# Arduino-Pro.net
KiCad netlist of a schematic drawn in EAGLE
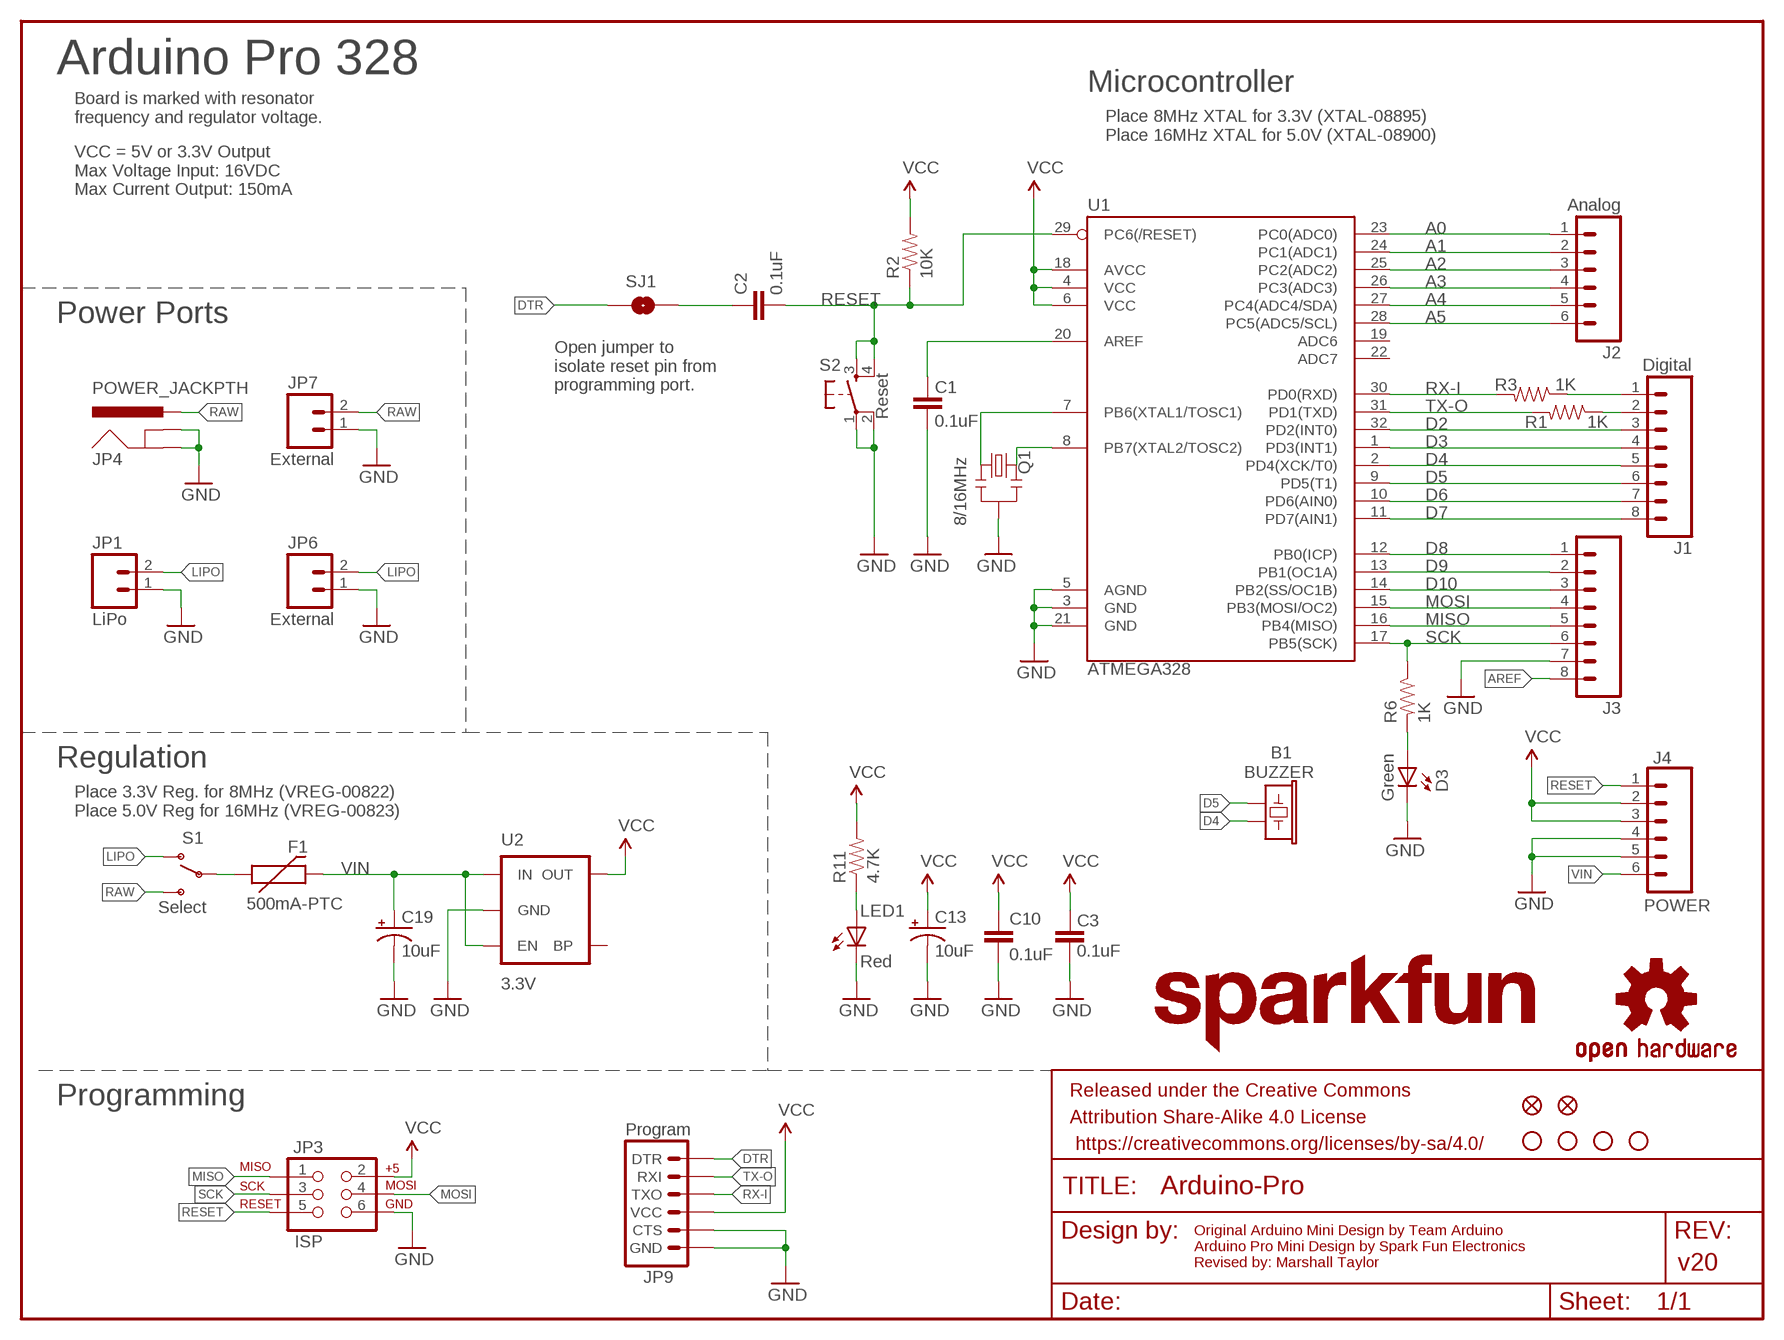
[diagram p0: schematic, sheet 1]

(export (version "E")
  (design (tool "Eeschema 10.0.6"))
  (components
    (comp (ref "B1")
      (value "BUZZER")
      (footprint "eagle-import:BUZZER-12MM-NS-KIT")
      (libsource (lib "eagle-import") (part "BUZZERPTH-NS-KIT"))
    )
    (comp (ref "C1")
      (value "0.1uF")
      (footprint "eagle-import:0402-CAP")
      (libsource (lib "eagle-import") (part "CAP0402-CAP"))
    )
    (comp (ref "C2")
      (value "0.1uF")
      (footprint "eagle-import:0402-CAP")
      (libsource (lib "eagle-import") (part "CAP0402-CAP"))
    )
    (comp (ref "C3")
      (value "0.1uF")
      (footprint "eagle-import:0402-CAP")
      (libsource (lib "eagle-import") (part "CAP0402-CAP"))
    )
    (comp (ref "C10")
      (value "0.1uF")
      (footprint "eagle-import:0402-CAP")
      (libsource (lib "eagle-import") (part "CAP0402-CAP"))
    )
    (comp (ref "C13")
      (value "10uF")
      (footprint "eagle-import:EIA3216")
      (libsource (lib "eagle-import") (part "CAP_POL1206"))
    )
    (comp (ref "C19")
      (value "10uF")
      (footprint "eagle-import:EIA3216")
      (libsource (lib "eagle-import") (part "CAP_POL1206"))
    )
    (comp (ref "D3")
      (value "Green")
      (footprint "eagle-import:LED-0603")
      (libsource (lib "eagle-import") (part "LED0603"))
    )
    (comp (ref "F1")
      (value "500mA-PTC")
      (footprint "eagle-import:PTC-1206")
      (libsource (lib "eagle-import") (part "PTCSMD"))
    )
    (comp (ref "FRAME2")
      (value "FRAME-LETTER")
      (footprint "eagle-import:CREATIVE_COMMONS")
      (libsource (lib "eagle-import") (part "FRAME-LETTER"))
    )
    (comp (ref "J1")
      (value "Digital")
      (footprint "eagle-import:1X08")
      (libsource (lib "eagle-import") (part "M081X08"))
    )
    (comp (ref "J2")
      (value "Analog")
      (footprint "eagle-import:1X06")
      (libsource (lib "eagle-import") (part "M06SIP"))
    )
    (comp (ref "J3")
      (value "M081X08")
      (footprint "eagle-import:1X08")
      (libsource (lib "eagle-import") (part "M081X08"))
    )
    (comp (ref "J4")
      (value "POWER")
      (footprint "eagle-import:1X06")
      (libsource (lib "eagle-import") (part "M06SIP"))
    )
    (comp (ref "JP1")
      (value "LiPo")
      (footprint "eagle-import:JST-2-SMD")
      (libsource (lib "eagle-import") (part "M02-JST-2MM-SMT"))
    )
    (comp (ref "JP2")
      (value "FIDUCIAL1X2.5")
      (footprint "eagle-import:FIDUCIAL-1X2.5")
      (libsource (lib "eagle-import") (part "FIDUCIAL1X2.5"))
    )
    (comp (ref "JP3")
      (value "ISP")
      (footprint "eagle-import:2X3")
      (libsource (lib "eagle-import") (part "AVR_SPI_PRG_6PTH"))
    )
    (comp (ref "JP4")
      (value "POWER_JACKPTH")
      (footprint "eagle-import:POWER_JACK_PTH")
      (libsource (lib "eagle-import") (part "POWER_JACKPTH"))
    )
    (comp (ref "JP5")
      (value "FIDUCIAL1X2.5")
      (footprint "eagle-import:FIDUCIAL-1X2.5")
      (libsource (lib "eagle-import") (part "FIDUCIAL1X2.5"))
    )
    (comp (ref "JP6")
      (value "External")
      (footprint "eagle-import:1X02")
      (libsource (lib "eagle-import") (part "M02PTH"))
    )
    (comp (ref "JP7")
      (value "External")
      (footprint "eagle-import:1X02")
      (libsource (lib "eagle-import") (part "M02PTH"))
    )
    (comp (ref "JP9")
      (value "Program")
      (footprint "eagle-import:1X06-SMD")
      (libsource (lib "eagle-import") (part "ARDUINO_SERIAL_PROGRAMSMD"))
    )
    (comp (ref "LED1")
      (value "Red")
      (footprint "eagle-import:LED-0603")
      (libsource (lib "eagle-import") (part "LED0603"))
    )
    (comp (ref "Q1")
      (value "8/16MHz")
      (footprint "eagle-import:RESONATOR-SMD")
      (libsource (lib "eagle-import") (part "RESONATORSMD"))
    )
    (comp (ref "R1")
      (value "1K")
      (footprint "eagle-import:0402-RES")
      (libsource (lib "eagle-import") (part "RESISTOR0402-RES"))
    )
    (comp (ref "R2")
      (value "10K")
      (footprint "eagle-import:0402-RES")
      (libsource (lib "eagle-import") (part "RESISTOR0402-RES"))
    )
    (comp (ref "R3")
      (value "1K")
      (footprint "eagle-import:0402-RES")
      (libsource (lib "eagle-import") (part "RESISTOR0402-RES"))
    )
    (comp (ref "R6")
      (value "1K")
      (footprint "eagle-import:0402-RES")
      (libsource (lib "eagle-import") (part "RESISTOR0402-RES"))
    )
    (comp (ref "R11")
      (value "4.7K")
      (footprint "eagle-import:0402-RES")
      (libsource (lib "eagle-import") (part "RESISTOR0402-RES"))
    )
    (comp (ref "S1")
      (value "Select")
      (footprint "eagle-import:SWITCH-SPST-SMD-A")
      (libsource (lib "eagle-import") (part "SWITCH-SPST-SMD-A"))
    )
    (comp (ref "S2")
      (value "Reset")
      (footprint "eagle-import:TACTILE_SWITCH_SMD")
      (libsource (lib "eagle-import") (part "TAC_SWITCHSMD"))
    )
    (comp (ref "SJ1")
      (value "SOLDERJUMPERNC3")
      (footprint "eagle-import:SJ_2S-NOTRACE")
      (libsource (lib "eagle-import") (part "SOLDERJUMPERNC2"))
    )
    (comp (ref "U$1")
      (value "STAND-OFF")
      (footprint "eagle-import:STAND-OFF")
      (libsource (lib "eagle-import") (part "STAND-OFF"))
    )
    (comp (ref "U$3")
      (value "STAND-OFF")
      (footprint "eagle-import:STAND-OFF")
      (libsource (lib "eagle-import") (part "STAND-OFF"))
    )
    (comp (ref "U$9")
      (value "STAND-OFF")
      (footprint "eagle-import:STAND-OFF")
      (libsource (lib "eagle-import") (part "STAND-OFF"))
    )
    (comp (ref "U$10")
      (value "STAND-OFF")
      (footprint "eagle-import:STAND-OFF")
      (libsource (lib "eagle-import") (part "STAND-OFF"))
    )
    (comp (ref "U1")
      (value "ATMEGA328")
      (footprint "eagle-import:TQFP32-08")
      (libsource (lib "eagle-import") (part "ATMEGA168"))
    )
    (comp (ref "U2")
      (value "3.3V")
      (footprint "eagle-import:SOT23-5")
      (libsource (lib "eagle-import") (part "V_REG_LDOSMD"))
    )
  )
  (nets
    (net (code "1") (name "/A0") (class "Default")
      (node (ref "J2") (pin "1") (pinfunction "1_1") (pintype "passive"))
      (node (ref "U1") (pin "23") (pinfunction "PC0(ADC0)_23") (pintype "bidirectional"))
    )
    (net (code "2") (name "/A1") (class "Default")
      (node (ref "J2") (pin "2") (pinfunction "2_2") (pintype "passive"))
      (node (ref "U1") (pin "24") (pinfunction "PC1(ADC1)_24") (pintype "bidirectional"))
    )
    (net (code "3") (name "/A2") (class "Default")
      (node (ref "J2") (pin "3") (pinfunction "3_3") (pintype "passive"))
      (node (ref "U1") (pin "25") (pinfunction "PC2(ADC2)_25") (pintype "bidirectional"))
    )
    (net (code "4") (name "/A3") (class "Default")
      (node (ref "J2") (pin "4") (pinfunction "4_4") (pintype "passive"))
      (node (ref "U1") (pin "26") (pinfunction "PC3(ADC3)_26") (pintype "bidirectional"))
    )
    (net (code "5") (name "/A4") (class "Default")
      (node (ref "J2") (pin "5") (pinfunction "5_5") (pintype "passive"))
      (node (ref "U1") (pin "27") (pinfunction "PC4(ADC4/SDA)_27") (pintype "bidirectional"))
    )
    (net (code "6") (name "/A5") (class "Default")
      (node (ref "J2") (pin "6") (pinfunction "6_6") (pintype "passive"))
      (node (ref "U1") (pin "28") (pinfunction "PC5(ADC5/SCL)_28") (pintype "bidirectional"))
    )
    (net (code "7") (name "/D2") (class "Default")
      (node (ref "J1") (pin "3") (pinfunction "3_3") (pintype "passive"))
      (node (ref "U1") (pin "32") (pinfunction "PD2(INT0)_32") (pintype "bidirectional"))
    )
    (net (code "8") (name "/D3") (class "Default")
      (node (ref "J1") (pin "4") (pinfunction "4_4") (pintype "passive"))
      (node (ref "U1") (pin "1") (pinfunction "PD3(INT1)_1") (pintype "bidirectional"))
    )
    (net (code "9") (name "/D6") (class "Default")
      (node (ref "J1") (pin "7") (pinfunction "7_7") (pintype "passive"))
      (node (ref "U1") (pin "10") (pinfunction "PD6(AIN0)_10") (pintype "bidirectional"))
    )
    (net (code "10") (name "/D7") (class "Default")
      (node (ref "J1") (pin "8") (pinfunction "8_8") (pintype "passive"))
      (node (ref "U1") (pin "11") (pinfunction "PD7(AIN1)_11") (pintype "bidirectional"))
    )
    (net (code "11") (name "/D8") (class "Default")
      (node (ref "J3") (pin "1") (pinfunction "1_1") (pintype "passive"))
      (node (ref "U1") (pin "12") (pinfunction "PB0(ICP)_12") (pintype "bidirectional"))
    )
    (net (code "12") (name "/D9") (class "Default")
      (node (ref "J3") (pin "2") (pinfunction "2_2") (pintype "passive"))
      (node (ref "U1") (pin "13") (pinfunction "PB1(OC1A)_13") (pintype "bidirectional"))
    )
    (net (code "13") (name "/D10") (class "Default")
      (node (ref "J3") (pin "3") (pinfunction "3_3") (pintype "passive"))
      (node (ref "U1") (pin "14") (pinfunction "PB2(SS/OC1B)_14") (pintype "bidirectional"))
    )
    (net (code "14") (name "AREF") (class "Default")
      (node (ref "C1") (pin "2") (pinfunction "2_2") (pintype "passive"))
      (node (ref "J3") (pin "8") (pinfunction "8_8") (pintype "passive"))
      (node (ref "U1") (pin "20") (pinfunction "AREF_20") (pintype "bidirectional"))
    )
    (net (code "15") (name "D4") (class "Default")
      (node (ref "B1") (pin "-") (pinfunction "2_-") (pintype "passive"))
      (node (ref "J1") (pin "5") (pinfunction "5_5") (pintype "passive"))
      (node (ref "U1") (pin "2") (pinfunction "PD4(XCK/T0)_2") (pintype "bidirectional"))
    )
    (net (code "16") (name "D5") (class "Default")
      (node (ref "B1") (pin "+") (pinfunction "1_+") (pintype "passive"))
      (node (ref "J1") (pin "6") (pinfunction "6_6") (pintype "passive"))
      (node (ref "U1") (pin "9") (pinfunction "PD5(T1)_9") (pintype "bidirectional"))
    )
    (net (code "17") (name "DTR") (class "Default")
      (node (ref "JP9") (pin "1") (pinfunction "DTR_1") (pintype "passive"))
      (node (ref "SJ1") (pin "1") (pinfunction "1_1") (pintype "passive"))
    )
    (net (code "18") (name "GND") (class "Default")
      (node (ref "C1") (pin "1") (pinfunction "1_1") (pintype "passive"))
      (node (ref "C10") (pin "2") (pinfunction "2_2") (pintype "passive"))
      (node (ref "C13") (pin "C") (pinfunction "-_C") (pintype "passive"))
      (node (ref "C19") (pin "C") (pinfunction "-_C") (pintype "passive"))
      (node (ref "C3") (pin "1") (pinfunction "1_1") (pintype "passive"))
      (node (ref "D3") (pin "C") (pinfunction "C_C") (pintype "passive"))
      (node (ref "J3") (pin "7") (pinfunction "7_7") (pintype "passive"))
      (node (ref "J4") (pin "4") (pinfunction "4_4") (pintype "passive"))
      (node (ref "J4") (pin "5") (pinfunction "5_5") (pintype "passive"))
      (node (ref "JP1") (pin "1") (pinfunction "1_1") (pintype "passive"))
      (node (ref "JP3") (pin "6") (pinfunction "6_6") (pintype "passive"))
      (node (ref "JP4") (pin "GND") (pinfunction "GND_GND") (pintype "bidirectional"))
      (node (ref "JP4") (pin "GNDBREAK") (pinfunction "GNDBREAK_GNDBREAK") (pintype "bidirectional"))
      (node (ref "JP6") (pin "1") (pinfunction "1_1") (pintype "passive"))
      (node (ref "JP7") (pin "1") (pinfunction "1_1") (pintype "passive"))
      (node (ref "JP9") (pin "5") (pinfunction "CTS_5") (pintype "passive"))
      (node (ref "JP9") (pin "6") (pinfunction "GND_6") (pintype "passive"))
      (node (ref "LED1") (pin "C") (pinfunction "C_C") (pintype "passive"))
      (node (ref "Q1") (pin "2") (pinfunction "2_2") (pintype "passive"))
      (node (ref "S2") (pin "1") (pinfunction "1_1") (pintype "passive"))
      (node (ref "S2") (pin "2") (pinfunction "2_2") (pintype "passive"))
      (node (ref "U1") (pin "21") (pinfunction "GND_21") (pintype "bidirectional"))
      (node (ref "U1") (pin "3") (pinfunction "GND_3") (pintype "bidirectional"))
      (node (ref "U1") (pin "5") (pinfunction "AGND_5") (pintype "bidirectional"))
      (node (ref "U2") (pin "2") (pinfunction "GND_2") (pintype "input"))
    )
    (net (code "19") (name "LIPO") (class "Default")
      (node (ref "JP1") (pin "2") (pinfunction "2_2") (pintype "passive"))
      (node (ref "JP6") (pin "2") (pinfunction "2_2") (pintype "passive"))
      (node (ref "S1") (pin "1") (pinfunction "O_1") (pintype "passive"))
    )
    (net (code "20") (name "MISO") (class "Default")
      (node (ref "J3") (pin "5") (pinfunction "5_5") (pintype "passive"))
      (node (ref "JP3") (pin "1") (pinfunction "1_1") (pintype "passive"))
      (node (ref "U1") (pin "16") (pinfunction "PB4(MISO)_16") (pintype "bidirectional"))
    )
    (net (code "21") (name "MOSI") (class "Default")
      (node (ref "J3") (pin "4") (pinfunction "4_4") (pintype "passive"))
      (node (ref "JP3") (pin "4") (pinfunction "4_4") (pintype "passive"))
      (node (ref "U1") (pin "15") (pinfunction "PB3(MOSI/OC2)_15") (pintype "bidirectional"))
    )
    (net (code "22") (name "Net-(C2-Pad1)") (class "Default")
      (node (ref "C2") (pin "1") (pinfunction "1_1") (pintype "passive"))
      (node (ref "SJ1") (pin "2") (pinfunction "2_2") (pintype "passive"))
    )
    (net (code "23") (name "Net-(D3-PadA)") (class "Default")
      (node (ref "D3") (pin "A") (pinfunction "A_A") (pintype "passive"))
      (node (ref "R6") (pin "2") (pinfunction "2_2") (pintype "passive"))
    )
    (net (code "24") (name "Net-(J1-Pad1)") (class "Default")
      (node (ref "J1") (pin "1") (pinfunction "1_1") (pintype "passive"))
      (node (ref "R3") (pin "1") (pinfunction "1_1") (pintype "passive"))
    )
    (net (code "25") (name "Net-(J1-Pad2)") (class "Default")
      (node (ref "J1") (pin "2") (pinfunction "2_2") (pintype "passive"))
      (node (ref "R1") (pin "1") (pinfunction "1_1") (pintype "passive"))
    )
    (net (code "26") (name "Net-(LED1-PadA)") (class "Default")
      (node (ref "LED1") (pin "A") (pinfunction "A_A") (pintype "passive"))
      (node (ref "R11") (pin "1") (pinfunction "1_1") (pintype "passive"))
    )
    (net (code "27") (name "Net-(S1-P)") (class "Default")
      (node (ref "F1") (pin "1") (pinfunction "1_1") (pintype "bidirectional"))
      (node (ref "S1") (pin "2") (pinfunction "P_2") (pintype "passive"))
    )
    (net (code "28") (name "Net-(U1-PB6(XTAL1{slash}TOSC1))") (class "Default")
      (node (ref "Q1") (pin "3") (pinfunction "3_3") (pintype "passive"))
      (node (ref "U1") (pin "7") (pinfunction "PB6(XTAL1/TOSC1)_7") (pintype "bidirectional"))
    )
    (net (code "29") (name "Net-(U1-PB7(XTAL2{slash}TOSC2))") (class "Default")
      (node (ref "Q1") (pin "1") (pinfunction "1_1") (pintype "passive"))
      (node (ref "U1") (pin "8") (pinfunction "PB7(XTAL2/TOSC2)_8") (pintype "bidirectional"))
    )
    (net (code "30") (name "RAW") (class "Default")
      (node (ref "JP4") (pin "PWR") (pinfunction "PWR_PWR") (pintype "bidirectional"))
      (node (ref "JP7") (pin "2") (pinfunction "2_2") (pintype "passive"))
      (node (ref "S1") (pin "3") (pinfunction "S_3") (pintype "passive"))
    )
    (net (code "31") (name "RESET") (class "Default")
      (node (ref "C2") (pin "2") (pinfunction "2_2") (pintype "passive"))
      (node (ref "J4") (pin "1") (pinfunction "1_1") (pintype "passive"))
      (node (ref "JP3") (pin "5") (pinfunction "5_5") (pintype "passive"))
      (node (ref "R2") (pin "1") (pinfunction "1_1") (pintype "passive"))
      (node (ref "S2") (pin "3") (pinfunction "3_3") (pintype "passive"))
      (node (ref "S2") (pin "4") (pinfunction "4_4") (pintype "passive"))
      (node (ref "U1") (pin "29") (pinfunction "PC6(/RESET)_29") (pintype "bidirectional"))
    )
    (net (code "32") (name "RX-I") (class "Default")
      (node (ref "JP9") (pin "3") (pinfunction "TXO_3") (pintype "passive"))
      (node (ref "R3") (pin "2") (pinfunction "2_2") (pintype "passive"))
      (node (ref "U1") (pin "30") (pinfunction "PD0(RXD)_30") (pintype "bidirectional"))
    )
    (net (code "33") (name "SCK") (class "Default")
      (node (ref "J3") (pin "6") (pinfunction "6_6") (pintype "passive"))
      (node (ref "JP3") (pin "3") (pinfunction "3_3") (pintype "passive"))
      (node (ref "R6") (pin "1") (pinfunction "1_1") (pintype "passive"))
      (node (ref "U1") (pin "17") (pinfunction "PB5(SCK)_17") (pintype "bidirectional"))
    )
    (net (code "34") (name "TX-O") (class "Default")
      (node (ref "JP9") (pin "2") (pinfunction "RXI_2") (pintype "passive"))
      (node (ref "R1") (pin "2") (pinfunction "2_2") (pintype "passive"))
      (node (ref "U1") (pin "31") (pinfunction "PD1(TXD)_31") (pintype "bidirectional"))
    )
    (net (code "35") (name "VCC") (class "Default")
      (node (ref "C10") (pin "1") (pinfunction "1_1") (pintype "passive"))
      (node (ref "C13") (pin "A") (pinfunction "+_A") (pintype "passive"))
      (node (ref "C3") (pin "2") (pinfunction "2_2") (pintype "passive"))
      (node (ref "J4") (pin "2") (pinfunction "2_2") (pintype "passive"))
      (node (ref "J4") (pin "3") (pinfunction "3_3") (pintype "passive"))
      (node (ref "JP3") (pin "2") (pinfunction "2_2") (pintype "passive"))
      (node (ref "JP9") (pin "4") (pinfunction "VCC_4") (pintype "passive"))
      (node (ref "R11") (pin "2") (pinfunction "2_2") (pintype "passive"))
      (node (ref "R2") (pin "2") (pinfunction "2_2") (pintype "passive"))
      (node (ref "U1") (pin "18") (pinfunction "AVCC_18") (pintype "bidirectional"))
      (node (ref "U1") (pin "4") (pinfunction "VCC_4") (pintype "bidirectional"))
      (node (ref "U1") (pin "6") (pinfunction "VCC_6") (pintype "bidirectional"))
      (node (ref "U2") (pin "5") (pinfunction "OUT_5") (pintype "passive"))
    )
    (net (code "36") (name "VIN") (class "Default")
      (node (ref "C19") (pin "A") (pinfunction "+_A") (pintype "passive"))
      (node (ref "F1") (pin "2") (pinfunction "2_2") (pintype "bidirectional"))
      (node (ref "J4") (pin "6") (pinfunction "6_6") (pintype "passive"))
      (node (ref "U2") (pin "1") (pinfunction "IN_1") (pintype "input"))
      (node (ref "U2") (pin "3") (pinfunction "EN_3") (pintype "input"))
    )
    (net (code "37") (name "unconnected-(U1-ADC6-Pad19)") (class "Default")
      (node (ref "U1") (pin "19") (pinfunction "ADC6_19") (pintype "bidirectional"))
    )
    (net (code "38") (name "unconnected-(U1-ADC7-Pad22)") (class "Default")
      (node (ref "U1") (pin "22") (pinfunction "ADC7_22") (pintype "bidirectional"))
    )
    (net (code "39") (name "unconnected-(U2-BP-Pad4)") (class "Default")
      (node (ref "U2") (pin "4") (pinfunction "BP_4") (pintype "input"))
    )
  )
)
